# AWR2243_ExPWR_RST_LEDs.net
KiCad netlist of a schematic drawn in Altium Designer
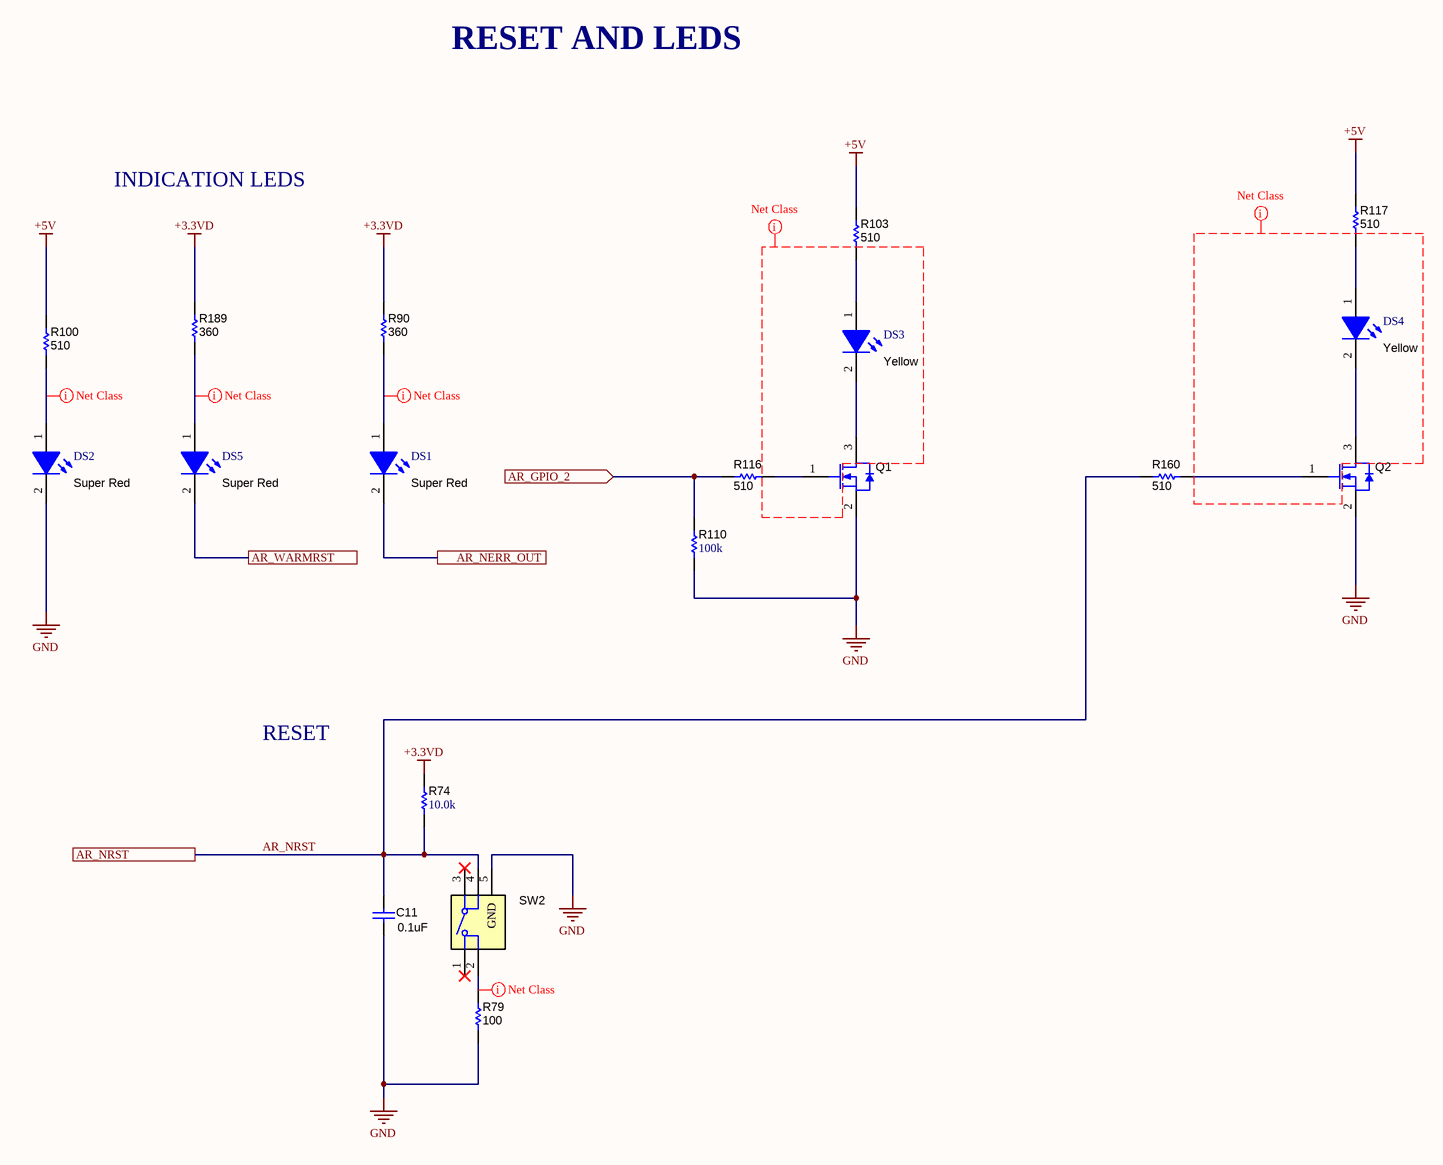
[diagram p0: AWR2243_ExPWR_RST_LEDs.SchDoc]

(export (version "E")
  (design (tool "Eeschema 10.0.6"))
  (components
    (comp (ref "C11")
      (value "GCM155R71C104KA55D")
      (footprint "0402L")
      (description "CAP, CERM, 0.1 uF, 16 V, +/- 10%, X7R, 0402")
      (fields
        (field (name "MANUFACTURER") "MuRata")
        (field (name "VALUEDISPLAYED") "0.1uF")
        (field (name "PUBLISHER") "Texas Instruments")
      )
      (libsource (lib "Altium Vault - TI") (part "Capacitor"))
    )
    (comp (ref "DS1")
      (value "Super Red")
      (footprint "SML-LX0603SRW_SuperRed")
      (description "LED, Super Red, SMD")
      (fields
        (field (name "MANUFACTURER") "Lumex")
        (field (name "PARTNUMBER") "SML-LX0603SRW-TR")
        (field (name "PUBLISHER") "Texas Instruments")
      )
      (libsource (lib "Altium Vault - TI") (part "CMP-0002876-1"))
    )
    (comp (ref "DS2")
      (value "Super Red")
      (footprint "SML-LX0603SRW_SuperRed")
      (description "LED, Super Red, SMD")
      (fields
        (field (name "MANUFACTURER") "Lumex")
        (field (name "PARTNUMBER") "SML-LX0603SRW-TR")
        (field (name "PUBLISHER") "Texas Instruments")
      )
      (libsource (lib "Altium Vault - TI") (part "CMP-0002876-1"))
    )
    (comp (ref "DS3")
      (value "Yellow")
      (footprint "SML-E1_Yellow")
      (description "LED, Yellow, SMD")
      (fields
        (field (name "MANUFACTURER") "Rohm")
        (field (name "PARTNUMBER") "SML-E12Y8WT86")
        (field (name "PUBLISHER") "Texas Instruments")
      )
      (libsource (lib "Altium Vault - TI") (part "LED"))
    )
    (comp (ref "DS4")
      (value "Yellow")
      (footprint "SML-E1_Yellow")
      (description "LED, Yellow, SMD")
      (fields
        (field (name "MANUFACTURER") "Rohm")
        (field (name "PARTNUMBER") "SML-E12Y8WT86")
        (field (name "PUBLISHER") "Texas Instruments")
      )
      (libsource (lib "Altium Vault - TI") (part "CMP-0002977-2"))
    )
    (comp (ref "DS5")
      (value "Super Red")
      (footprint "SML-LX0603SRW_SuperRed")
      (description "LED, Super Red, SMD")
      (fields
        (field (name "MANUFACTURER") "Lumex")
        (field (name "PARTNUMBER") "SML-LX0603SRW-TR")
        (field (name "PUBLISHER") "Texas Instruments")
      )
      (libsource (lib "Altium Vault - TI") (part "CMP-0002876-1"))
    )
    (comp (ref "Q1")
      (value "BSS123")
      (footprint "SOT-23")
      (description "MOSFET, N-CH, 100 V, 0.17 A, SOT-23")
      (fields
        (field (name "MANUFACTURER") "Fairchild Semiconductor")
        (field (name "PUBLISHER") "Texas Instruments")
      )
      (libsource (lib "Altium Vault - TI") (part "MOSFET_N_D3G1S2"))
    )
    (comp (ref "Q2")
      (value "BSS123")
      (footprint "SOT-23")
      (description "MOSFET, N-CH, 100 V, 0.17 A, SOT-23")
      (fields
        (field (name "MANUFACTURER") "Fairchild Semiconductor")
        (field (name "PUBLISHER") "Texas Instruments")
      )
      (libsource (lib "Altium Vault - TI") (part "MOSFET_N_D3G1S2"))
    )
    (comp (ref "R74")
      (value "CRCW040210K0FKED")
      (footprint "0402L")
      (description "RES, 10.0 k, 1%, 0.063 W, AEC-Q200 Grade 0, 0402")
      (fields (field (name "MANUFACTURER") "Vishay-Dale") (field (name "VALUEDISPLAYED") "10.0k"))
      (libsource (lib "Altium Vault - TI") (part "Resistor"))
    )
    (comp (ref "R79")
      (value "ERJ-2GEJ101X")
      (footprint "0402L")
      (description "RES, 100, 5%, 0.1 W, AEC-Q200 Grade 0, 0402")
      (fields
        (field (name "MANUFACTURER") "Panasonic")
        (field (name "VALUEDISPLAYED") "100")
        (field (name "PUBLISHER") "Texas Instruments")
      )
      (libsource (lib "Altium Vault - TI") (part "Resistor"))
    )
    (comp (ref "R90")
      (value "ERJ-2GEJ361X")
      (footprint "0402L")
      (description "RES, 360, 5%, 0.1 W, AEC-Q200 Grade 0, 0402")
      (fields (field (name "MANUFACTURER") "Panasonic") (field (name "VALUEDISPLAYED") "360"))
      (libsource (lib "Altium Vault - TI") (part "Resistor"))
    )
    (comp (ref "R100")
      (value "ERJ-2GEJ511X")
      (footprint "0402L")
      (description "RES, 510, 5%, 0.1 W, AEC-Q200 Grade 0, 0402")
      (fields (field (name "MANUFACTURER") "Panasonic") (field (name "VALUEDISPLAYED") "510"))
      (libsource (lib "Altium Vault - TI") (part "Resistor"))
    )
    (comp (ref "R103")
      (value "ERJ-2GEJ511X")
      (footprint "0402L")
      (description "RES, 510, 5%, 0.1 W, AEC-Q200 Grade 0, 0402")
      (fields (field (name "MANUFACTURER") "Panasonic") (field (name "VALUEDISPLAYED") "510"))
      (libsource (lib "Altium Vault - TI") (part "Resistor"))
    )
    (comp (ref "R110")
      (value "CRCW0402100KFKED")
      (footprint "0402L")
      (description "RES, 100 k, 1%, 0.063 W, AEC-Q200 Grade 0, 0402")
      (fields (field (name "MANUFACTURER") "Vishay-Dale") (field (name "VALUEDISPLAYED") "100k"))
      (libsource (lib "Altium Vault - TI") (part "Resistor"))
    )
    (comp (ref "R116")
      (value "ERJ-2GEJ511X")
      (footprint "0402L")
      (description "RES, 510, 5%, 0.1 W, AEC-Q200 Grade 0, 0402")
      (fields (field (name "MANUFACTURER") "Panasonic") (field (name "VALUEDISPLAYED") "510"))
      (libsource (lib "Altium Vault - TI") (part "Resistor"))
    )
    (comp (ref "R117")
      (value "ERJ-2GEJ511X")
      (footprint "0402L")
      (description "RES, 510, 5%, 0.1 W, AEC-Q200 Grade 0, 0402")
      (fields (field (name "MANUFACTURER") "Panasonic") (field (name "VALUEDISPLAYED") "510"))
      (libsource (lib "Altium Vault - TI") (part "Resistor"))
    )
    (comp (ref "R160")
      (value "ERJ-2GEJ511X")
      (footprint "0402L")
      (description "RES, 510, 5%, 0.1 W, AEC-Q200 Grade 0, 0402")
      (fields (field (name "MANUFACTURER") "Panasonic") (field (name "VALUEDISPLAYED") "510"))
      (libsource (lib "Altium Vault - TI") (part "Resistor"))
    )
    (comp (ref "R189")
      (value "ERJ-2GEJ361X")
      (footprint "0402L")
      (description "RES, 360, 5%, 0.1 W, AEC-Q200 Grade 0, 0402")
      (fields (field (name "MANUFACTURER") "Panasonic") (field (name "VALUEDISPLAYED") "360"))
      (libsource (lib "Altium Vault - TI") (part "Resistor"))
    )
    (comp (ref "SW2")
      (value "KMR243GLFG")
      (footprint "SW_KMR243GLFG")
      (description "Switch, SPST-NO, Off-Mom, 0.01 A, 32 VDC, SMD")
      (fields (field (name "MANUFACTURER") "C&K Components") (field (name "PUBLISHER") "Texas Instruments"))
      (libsource (lib "Altium Vault - TI") (part "CMP-0002325-1"))
    )
  )
  (nets
    (net (code "1") (name "+3.3VD") (class "Default")
      (node (ref "R189") (pin "2") (pinfunction "2_2") (pintype "passive"))
      (node (ref "R74") (pin "2") (pinfunction "2_2") (pintype "passive"))
      (node (ref "R90") (pin "2") (pinfunction "2_2") (pintype "passive"))
    )
    (net (code "2") (name "+5V") (class "Default")
      (node (ref "R100") (pin "2") (pinfunction "2_2") (pintype "passive"))
      (node (ref "R103") (pin "2") (pinfunction "2_2") (pintype "passive"))
      (node (ref "R117") (pin "2") (pinfunction "2_2") (pintype "passive"))
    )
    (net (code "3") (name "/AR_GPIO_2") (class "Default")
      (node (ref "R110") (pin "2") (pinfunction "2_2") (pintype "passive"))
      (node (ref "R116") (pin "1") (pinfunction "1_1") (pintype "passive"))
    )
    (net (code "4") (name "/AR_NERR_OUT") (class "Default")
      (node (ref "DS1") (pin "2") (pinfunction "K_2") (pintype "passive"))
    )
    (net (code "5") (name "/AR_NRST") (class "Default")
      (node (ref "C11") (pin "2") (pinfunction "2_2") (pintype "passive"))
      (node (ref "R160") (pin "1") (pinfunction "1_1") (pintype "passive"))
      (node (ref "R74") (pin "1") (pinfunction "1_1") (pintype "passive"))
      (node (ref "SW2") (pin "4") (pinfunction "4_4") (pintype "passive"))
    )
    (net (code "6") (name "/AR_WARMRST") (class "Default")
      (node (ref "DS5") (pin "2") (pinfunction "K_2") (pintype "passive"))
    )
    (net (code "7") (name "GND") (class "Default")
      (node (ref "C11") (pin "1") (pinfunction "1_1") (pintype "passive"))
      (node (ref "DS2") (pin "2") (pinfunction "K_2") (pintype "passive"))
      (node (ref "Q1") (pin "2") (pinfunction "S_2") (pintype "passive"))
      (node (ref "Q2") (pin "2") (pinfunction "S_2") (pintype "passive"))
      (node (ref "R110") (pin "1") (pinfunction "1_1") (pintype "passive"))
      (node (ref "R79") (pin "1") (pinfunction "1_1") (pintype "passive"))
      (node (ref "SW2") (pin "5") (pinfunction "GND_5") (pintype "passive"))
    )
    (net (code "8") (name "Net-(DS1-A)") (class "Default")
      (node (ref "DS1") (pin "1") (pinfunction "A_1") (pintype "passive"))
      (node (ref "R90") (pin "1") (pinfunction "1_1") (pintype "passive"))
    )
    (net (code "9") (name "Net-(DS2-A)") (class "Default")
      (node (ref "DS2") (pin "1") (pinfunction "A_1") (pintype "passive"))
      (node (ref "R100") (pin "1") (pinfunction "1_1") (pintype "passive"))
    )
    (net (code "10") (name "Net-(DS3-A)") (class "Default")
      (node (ref "DS3") (pin "1") (pinfunction "A_1") (pintype "passive"))
      (node (ref "R103") (pin "1") (pinfunction "1_1") (pintype "passive"))
    )
    (net (code "11") (name "Net-(DS3-K)") (class "Default")
      (node (ref "DS3") (pin "2") (pinfunction "K_2") (pintype "passive"))
      (node (ref "Q1") (pin "3") (pinfunction "D_3") (pintype "passive"))
    )
    (net (code "12") (name "Net-(DS4-A)") (class "Default")
      (node (ref "DS4") (pin "1") (pinfunction "A_1") (pintype "passive"))
      (node (ref "R117") (pin "1") (pinfunction "1_1") (pintype "passive"))
    )
    (net (code "13") (name "Net-(DS4-K)") (class "Default")
      (node (ref "DS4") (pin "2") (pinfunction "K_2") (pintype "passive"))
      (node (ref "Q2") (pin "3") (pinfunction "D_3") (pintype "passive"))
    )
    (net (code "14") (name "Net-(DS5-A)") (class "Default")
      (node (ref "DS5") (pin "1") (pinfunction "A_1") (pintype "passive"))
      (node (ref "R189") (pin "1") (pinfunction "1_1") (pintype "passive"))
    )
    (net (code "15") (name "Net-(Q1-G)") (class "Default")
      (node (ref "Q1") (pin "1") (pinfunction "G_1") (pintype "passive"))
      (node (ref "R116") (pin "2") (pinfunction "2_2") (pintype "passive"))
    )
    (net (code "16") (name "Net-(Q2-G)") (class "Default")
      (node (ref "Q2") (pin "1") (pinfunction "G_1") (pintype "passive"))
      (node (ref "R160") (pin "2") (pinfunction "2_2") (pintype "passive"))
    )
    (net (code "17") (name "Net-(R79-Pad2)") (class "Default")
      (node (ref "R79") (pin "2") (pinfunction "2_2") (pintype "passive"))
      (node (ref "SW2") (pin "2") (pinfunction "2_2") (pintype "passive"))
    )
    (net (code "18") (name "unconnected-(SW2-Pad1)") (class "Default")
      (node (ref "SW2") (pin "1") (pinfunction "1_1") (pintype "passive+no_connect"))
    )
    (net (code "19") (name "unconnected-(SW2-Pad3)") (class "Default")
      (node (ref "SW2") (pin "3") (pinfunction "3_3") (pintype "passive+no_connect"))
    )
  )
)
